# Segger_JTAG_v1p1.net
KiCad netlist of a schematic drawn in EAGLE
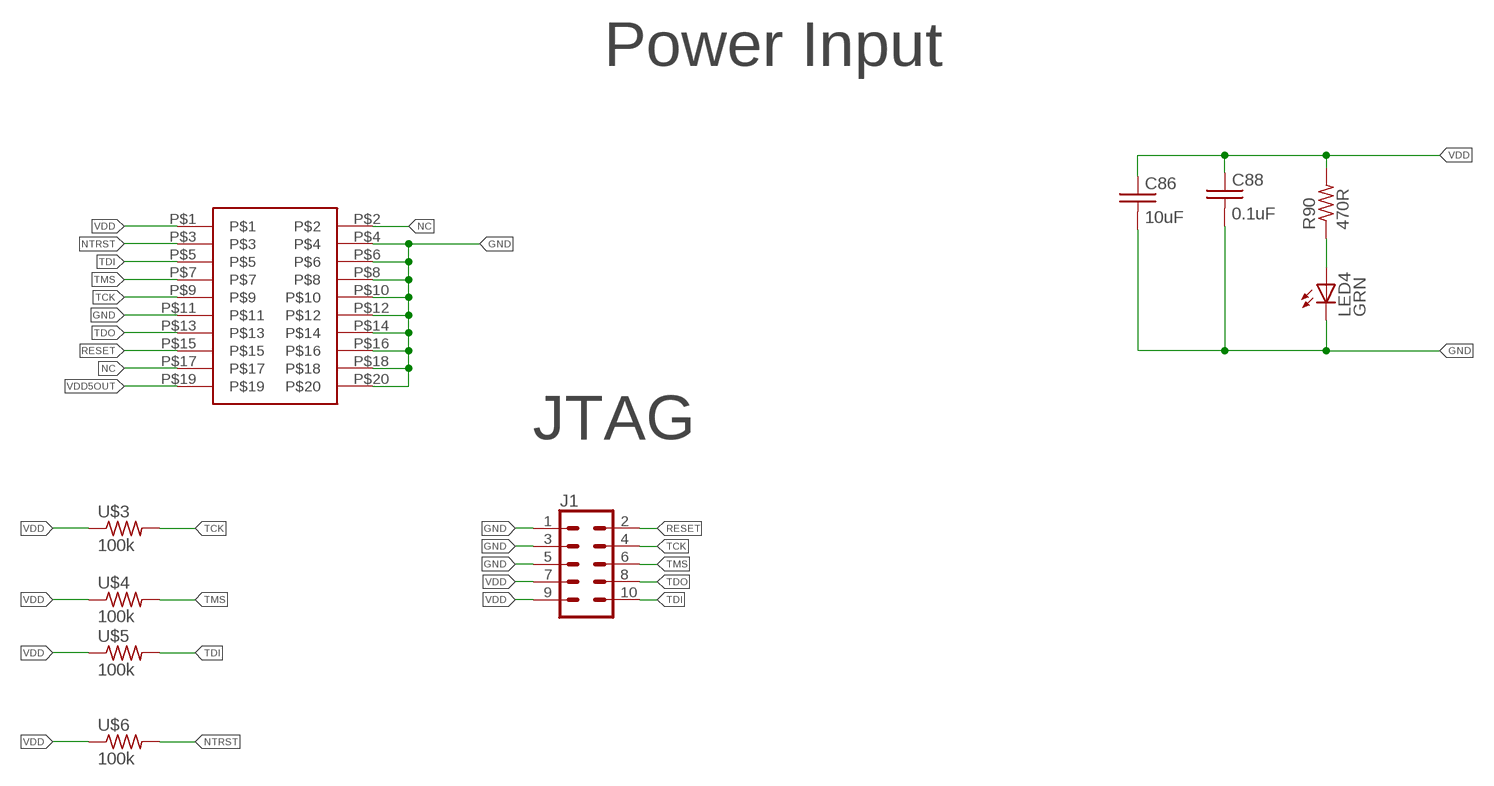
[diagram p0: schematic, sheet 1]

(export (version "E")
  (design (tool "Eeschema 10.0.6"))
  (components
    (comp (ref "C86")
      (value "10uF")
      (footprint "eagle-import:0805")
      (libsource (lib "eagle-import") (part "C_0805"))
    )
    (comp (ref "C88")
      (value "0.1uF")
      (footprint "eagle-import:0805")
      (libsource (lib "eagle-import") (part "C_0805"))
    )
    (comp (ref "J1")
      (value "CONN_05X2SHD")
      (footprint "eagle-import:2X5-SHROUDED")
      (libsource (lib "eagle-import") (part "CONN_05X2SHD"))
    )
    (comp (ref "LED4")
      (value "LED_0805_GREEN")
      (footprint "eagle-import:LED_0805_GREEN")
      (libsource (lib "eagle-import") (part "LED_0805_GREEN"))
    )
    (comp (ref "R90")
      (value "470R")
      (footprint "eagle-import:0805")
      (libsource (lib "eagle-import") (part "R_0805"))
    )
    (comp (ref "U$2")
      (value "2_X_10_HEADER_GENERIC")
      (footprint "eagle-import:2_X_10_.1_INCH")
      (libsource (lib "eagle-import") (part "2_X_10_HEADER_GENERIC"))
    )
    (comp (ref "U$3")
      (value "100k")
      (footprint "eagle-import:0805")
      (libsource (lib "eagle-import") (part "R_0805"))
    )
    (comp (ref "U$4")
      (value "100k")
      (footprint "eagle-import:0805")
      (libsource (lib "eagle-import") (part "R_0805"))
    )
    (comp (ref "U$5")
      (value "100k")
      (footprint "eagle-import:0805")
      (libsource (lib "eagle-import") (part "R_0805"))
    )
    (comp (ref "U$6")
      (value "100k")
      (footprint "eagle-import:0805")
      (libsource (lib "eagle-import") (part "R_0805"))
    )
  )
  (nets
    (net (code "1") (name "GND") (class "Default")
      (node (ref "C86") (pin "2") (pinfunction "2_2") (pintype "passive"))
      (node (ref "C88") (pin "2") (pinfunction "2_2") (pintype "passive"))
      (node (ref "J1") (pin "1") (pinfunction "1_1") (pintype "passive"))
      (node (ref "J1") (pin "3") (pinfunction "3_3") (pintype "passive"))
      (node (ref "J1") (pin "5") (pinfunction "5_5") (pintype "passive"))
      (node (ref "LED4") (pin "C") (pinfunction "C_C") (pintype "passive"))
      (node (ref "U$2") (pin "P$10") (pinfunction "P$10_P$10") (pintype "bidirectional"))
      (node (ref "U$2") (pin "P$11") (pinfunction "P$11_P$11") (pintype "bidirectional"))
      (node (ref "U$2") (pin "P$12") (pinfunction "P$12_P$12") (pintype "bidirectional"))
      (node (ref "U$2") (pin "P$14") (pinfunction "P$14_P$14") (pintype "bidirectional"))
      (node (ref "U$2") (pin "P$16") (pinfunction "P$16_P$16") (pintype "bidirectional"))
      (node (ref "U$2") (pin "P$18") (pinfunction "P$18_P$18") (pintype "bidirectional"))
      (node (ref "U$2") (pin "P$20") (pinfunction "P$20_P$20") (pintype "bidirectional"))
      (node (ref "U$2") (pin "P$4") (pinfunction "P$4_P$4") (pintype "bidirectional"))
      (node (ref "U$2") (pin "P$6") (pinfunction "P$6_P$6") (pintype "bidirectional"))
      (node (ref "U$2") (pin "P$8") (pinfunction "P$8_P$8") (pintype "bidirectional"))
    )
    (net (code "2") (name "NC") (class "Default")
      (node (ref "U$2") (pin "P$17") (pinfunction "P$17_P$17") (pintype "bidirectional"))
      (node (ref "U$2") (pin "P$2") (pinfunction "P$2_P$2") (pintype "bidirectional"))
    )
    (net (code "3") (name "NTRST") (class "Default")
      (node (ref "U$2") (pin "P$3") (pinfunction "P$3_P$3") (pintype "bidirectional"))
      (node (ref "U$6") (pin "2") (pinfunction "2_2") (pintype "passive"))
    )
    (net (code "4") (name "Net-(LED4-PadA)") (class "Default")
      (node (ref "LED4") (pin "A") (pinfunction "A_A") (pintype "passive"))
      (node (ref "R90") (pin "1") (pinfunction "1_1") (pintype "passive"))
    )
    (net (code "5") (name "RESET") (class "Default")
      (node (ref "J1") (pin "2") (pinfunction "2_2") (pintype "passive"))
      (node (ref "U$2") (pin "P$15") (pinfunction "P$15_P$15") (pintype "bidirectional"))
    )
    (net (code "6") (name "TCK") (class "Default")
      (node (ref "J1") (pin "4") (pinfunction "4_4") (pintype "passive"))
      (node (ref "U$2") (pin "P$9") (pinfunction "P$9_P$9") (pintype "bidirectional"))
      (node (ref "U$3") (pin "2") (pinfunction "2_2") (pintype "passive"))
    )
    (net (code "7") (name "TDI") (class "Default")
      (node (ref "J1") (pin "10") (pinfunction "10_10") (pintype "passive"))
      (node (ref "U$2") (pin "P$5") (pinfunction "P$5_P$5") (pintype "bidirectional"))
      (node (ref "U$5") (pin "2") (pinfunction "2_2") (pintype "passive"))
    )
    (net (code "8") (name "TDO") (class "Default")
      (node (ref "J1") (pin "8") (pinfunction "8_8") (pintype "passive"))
      (node (ref "U$2") (pin "P$13") (pinfunction "P$13_P$13") (pintype "bidirectional"))
    )
    (net (code "9") (name "TMS") (class "Default")
      (node (ref "J1") (pin "6") (pinfunction "6_6") (pintype "passive"))
      (node (ref "U$2") (pin "P$7") (pinfunction "P$7_P$7") (pintype "bidirectional"))
      (node (ref "U$4") (pin "2") (pinfunction "2_2") (pintype "passive"))
    )
    (net (code "10") (name "VDD") (class "Default")
      (node (ref "C86") (pin "1") (pinfunction "1_1") (pintype "passive"))
      (node (ref "C88") (pin "1") (pinfunction "1_1") (pintype "passive"))
      (node (ref "J1") (pin "7") (pinfunction "7_7") (pintype "passive"))
      (node (ref "J1") (pin "9") (pinfunction "9_9") (pintype "passive"))
      (node (ref "R90") (pin "2") (pinfunction "2_2") (pintype "passive"))
      (node (ref "U$2") (pin "P$1") (pinfunction "P$1_P$1") (pintype "bidirectional"))
      (node (ref "U$3") (pin "1") (pinfunction "1_1") (pintype "passive"))
      (node (ref "U$4") (pin "1") (pinfunction "1_1") (pintype "passive"))
      (node (ref "U$5") (pin "1") (pinfunction "1_1") (pintype "passive"))
      (node (ref "U$6") (pin "1") (pinfunction "1_1") (pintype "passive"))
    )
    (net (code "11") (name "VDD5OUT") (class "Default")
      (node (ref "U$2") (pin "P$19") (pinfunction "P$19_P$19") (pintype "bidirectional"))
    )
  )
)
